# Schematic.net
KiCad netlist of a schematic drawn in Altium Designer
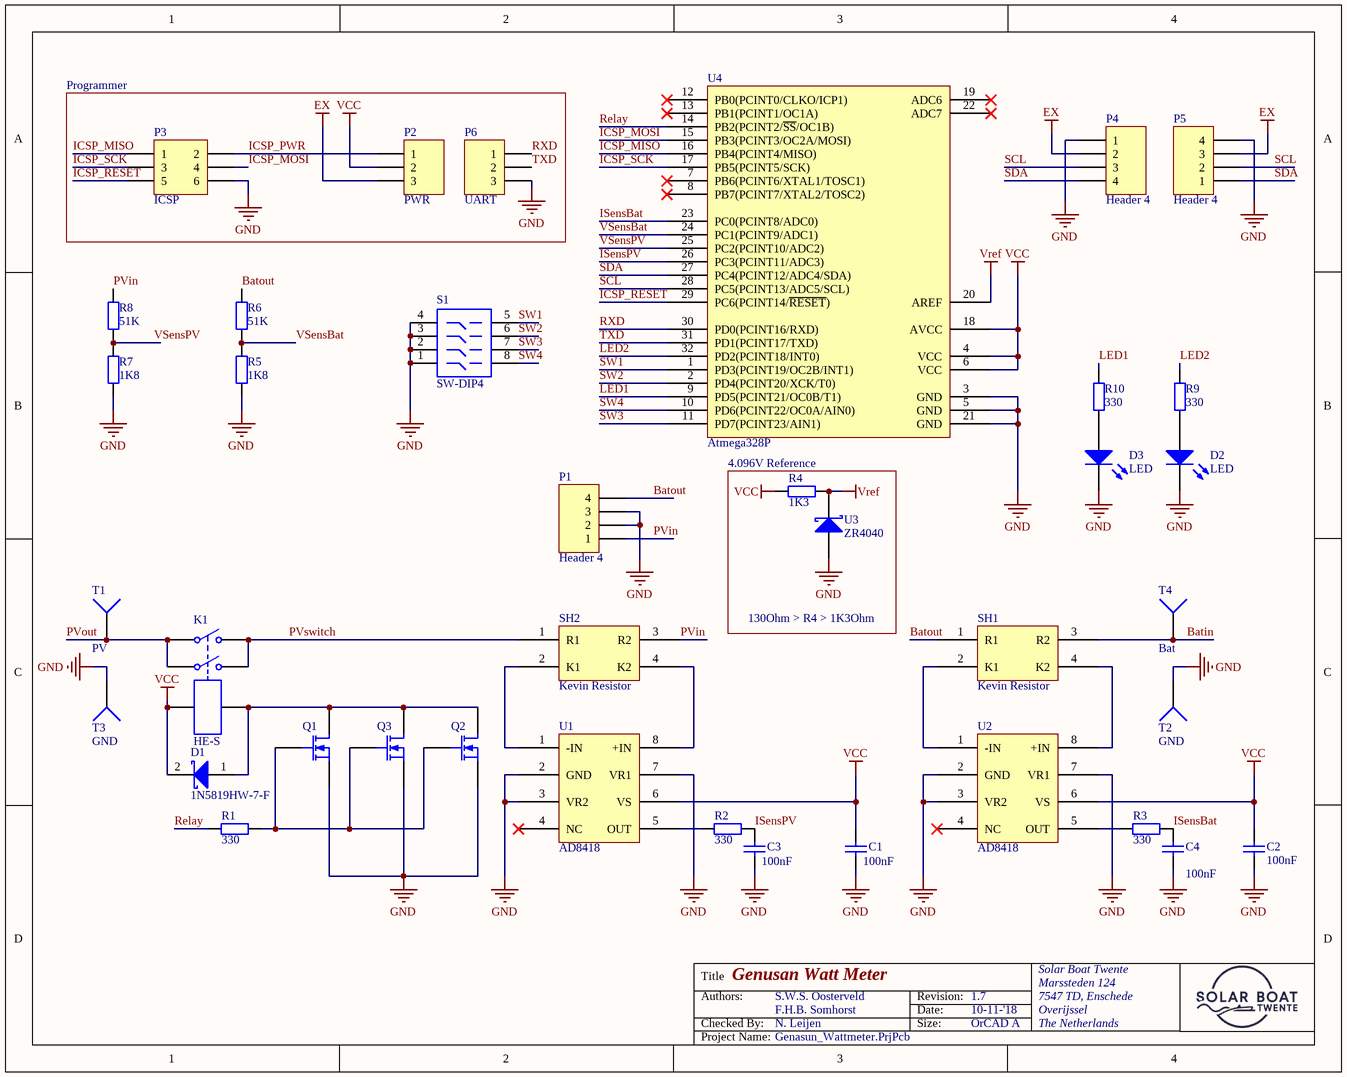
[diagram p0: Schematic.SchDoc]

(export (version "E")
  (design (tool "Eeschema 10.0.6"))
  (components
    (comp (ref "C1")
      (value "100nF")
      (footprint "CAP 0805/2012")
      (description "Capacitor")
      (fields (field (name "Comment") "Cap") (field (name "PUBLISHER") "Altium Limited"))
      (libsource (lib "Miscellaneous Devices") (part "Cap"))
    )
    (comp (ref "C2")
      (value "100nF")
      (footprint "CAP 0805/2012")
      (description "Capacitor")
      (fields (field (name "Comment") "Cap") (field (name "PUBLISHER") "Altium Limited"))
      (libsource (lib "Miscellaneous Devices") (part "Cap"))
    )
    (comp (ref "C3")
      (value "100nF")
      (footprint "CAP 0805/2012")
      (description "Capacitor")
      (fields (field (name "Comment") "Cap") (field (name "PUBLISHER") "Altium Limited"))
      (libsource (lib "Miscellaneous Devices") (part "Cap"))
    )
    (comp (ref "C4")
      (value "100nF")
      (footprint "CAP 0805/2012")
      (description "Capacitor")
      (fields (field (name "Comment") "Cap") (field (name "PUBLISHER") "Altium Limited"))
      (libsource (lib "Miscellaneous Devices") (part "Cap"))
    )
    (comp (ref "D1")
      (value "1N5819HW-7-F")
      (footprint "DIOD-SOD-123-2_V")
      (fields (field (name "MANUFACTURER") "Diodes Inc"))
      (libsource (lib "Altium Content Vault") (part "DIOD-DSKY-A1K2-2"))
    )
    (comp (ref "D2")
      (value "LED")
      (footprint "LED 0805/2012 RED")
      (description "Typical INFRARED GaAs LED")
      (fields (field (name "PUBLISHER") "Altium Limited"))
      (libsource (lib "Miscellaneous Devices") (part "LED0"))
    )
    (comp (ref "D3")
      (value "LED")
      (footprint "LED 0805/2012 RED")
      (description "Typical INFRARED GaAs LED")
      (fields (field (name "PUBLISHER") "Altium Limited"))
      (libsource (lib "Miscellaneous Devices") (part "LED0"))
    )
    (comp (ref "K1")
      (value "HE-S")
      (footprint "Relay HE-S Parasonic")
      (description "Dual-Pole Single-Throw Relay")
      (fields (field (name "PUBLISHER") "Altium Limited"))
      (libsource (lib "Miscellaneous Devices") (part "Relay-DPST"))
    )
    (comp (ref "P1")
      (value "Header 4")
      (footprint "4Pin 6.35mm Connector")
      (description "Header, 4-Pin")
      (fields (field (name "PUBLISHER") "Altium Limited"))
      (libsource (lib "Miscellaneous Connectors") (part "Header 4"))
    )
    (comp (ref "P2")
      (value "PWR")
      (footprint "HDR1X3")
      (description "Header, 3-Pin")
      (fields (field (name "PUBLISHER") "Altium Limited"))
      (libsource (lib "") (part "Header 3_1"))
    )
    (comp (ref "P3")
      (value "ICSP")
      (footprint "HDR2X3")
      (description "Header, 3-Pin, Dual row")
      (fields (field (name "PUBLISHER") "Altium Limited"))
      (libsource (lib "Miscellaneous Connectors") (part "Header 3X2"))
    )
    (comp (ref "P4")
      (value "Header 4")
      (footprint "TE 282834-4")
      (description "Header, 4-Pin")
      (fields (field (name "PUBLISHER") "Altium Limited"))
      (libsource (lib "") (part "Header 4_1"))
    )
    (comp (ref "P5")
      (value "Header 4")
      (footprint "TE 282834-4")
      (description "Header, 4-Pin")
      (fields (field (name "PUBLISHER") "Altium Limited"))
      (libsource (lib "Miscellaneous Connectors") (part "Header 4"))
    )
    (comp (ref "P6")
      (value "UART")
      (footprint "HDR1X3H")
      (description "Header, 3-Pin")
      (fields (field (name "PUBLISHER") "Altium Limited"))
      (libsource (lib "Miscellaneous Connectors") (part "Header 3"))
    )
    (comp (ref "Q1")
      (value "MOSFET-N")
      (footprint "DIODES SOT-23-3")
      (description "N-Channel MOSFET")
      (fields (field (name "PUBLISHER") "Altium Limited"))
      (libsource (lib "Miscellaneous Devices") (part "MOSFET-N"))
    )
    (comp (ref "Q2")
      (value "MOSFET-N")
      (footprint "DIODES SOT-23-3")
      (description "N-Channel MOSFET")
      (fields (field (name "PUBLISHER") "Altium Limited"))
      (libsource (lib "Miscellaneous Devices") (part "MOSFET-N"))
    )
    (comp (ref "Q3")
      (value "MOSFET-N")
      (footprint "DIODES SOT-23-3")
      (description "N-Channel MOSFET")
      (fields (field (name "PUBLISHER") "Altium Limited"))
      (libsource (lib "Miscellaneous Devices") (part "MOSFET-N"))
    )
    (comp (ref "R1")
      (value "330")
      (footprint "RES 0805/2012")
      (description "Resistor")
      (fields (field (name "Comment") "Res2") (field (name "PUBLISHER") "Altium Limited"))
      (libsource (lib "") (part "Res2_1"))
    )
    (comp (ref "R2")
      (value "330")
      (footprint "RES 0805/2012")
      (description "Resistor")
      (fields (field (name "Comment") "Res2") (field (name "PUBLISHER") "Altium Limited"))
      (libsource (lib "") (part "Res2_1"))
    )
    (comp (ref "R3")
      (value "330")
      (footprint "RES 0805/2012")
      (description "Resistor")
      (fields (field (name "Comment") "Res2") (field (name "PUBLISHER") "Altium Limited"))
      (libsource (lib "") (part "Res2_1"))
    )
    (comp (ref "R4")
      (value "1K3")
      (footprint "RES 0805/2012")
      (description "Resistor")
      (fields (field (name "Comment") "Res2") (field (name "PUBLISHER") "Altium Limited"))
      (libsource (lib "") (part "Res2_1"))
    )
    (comp (ref "R5")
      (value "1K8")
      (footprint "RES 0805/2012")
      (description "Resistor")
      (fields (field (name "Comment") "Res2") (field (name "PUBLISHER") "Altium Limited"))
      (libsource (lib "Miscellaneous Devices") (part "Res2"))
    )
    (comp (ref "R6")
      (value "51K")
      (footprint "RES 0805/2012")
      (description "Resistor")
      (fields (field (name "Comment") "Res2") (field (name "PUBLISHER") "Altium Limited"))
      (libsource (lib "Miscellaneous Devices") (part "Res2"))
    )
    (comp (ref "R7")
      (value "1K8")
      (footprint "RES 0805/2012")
      (description "Resistor")
      (fields (field (name "Comment") "Res2") (field (name "PUBLISHER") "Altium Limited"))
      (libsource (lib "Miscellaneous Devices") (part "Res2"))
    )
    (comp (ref "R8")
      (value "51K")
      (footprint "RES 0805/2012")
      (description "Resistor")
      (fields (field (name "Comment") "Res2") (field (name "PUBLISHER") "Altium Limited"))
      (libsource (lib "Miscellaneous Devices") (part "Res2"))
    )
    (comp (ref "R9")
      (value "330")
      (footprint "RES 0805/2012")
      (description "Resistor")
      (fields (field (name "Comment") "Res2") (field (name "PUBLISHER") "Altium Limited"))
      (libsource (lib "Miscellaneous Devices") (part "Res2"))
    )
    (comp (ref "R10")
      (value "330")
      (footprint "RES 0805/2012")
      (description "Resistor")
      (fields (field (name "Comment") "Res2") (field (name "PUBLISHER") "Altium Limited"))
      (libsource (lib "Miscellaneous Devices") (part "Res2"))
    )
    (comp (ref "S1")
      (value "SW-DIP4")
      (footprint "DIP-8")
      (description "DIP Switch")
      (fields (field (name "PUBLISHER") "Altium Limited"))
      (libsource (lib "Miscellaneous Devices") (part "SW-DIP4"))
    )
    (comp (ref "SH1")
      (value "Kevin Resistor")
      (footprint "TE TLR Shunt")
      (libsource (lib "Personal Library") (part "Kevin Resistor"))
    )
    (comp (ref "SH2")
      (value "Kevin Resistor")
      (footprint "TE TLR Shunt")
      (libsource (lib "Personal Library") (part "Kevin Resistor"))
    )
    (comp (ref "T1")
      (value "PV")
      (footprint "PCB_Pin_Outsteeksel")
      (description "Socket")
      (fields (field (name "PUBLISHER") "Altium Limited"))
      (libsource (lib "Miscellaneous Connectors") (part "Socket"))
    )
    (comp (ref "T2")
      (value "GND")
      (footprint "PCB_Pin_Outsteeksel")
      (description "Socket")
      (fields (field (name "PUBLISHER") "Altium Limited"))
      (libsource (lib "Miscellaneous Connectors") (part "Socket"))
    )
    (comp (ref "T3")
      (value "GND")
      (footprint "PCB_Pin_Outsteeksel")
      (description "Socket")
      (fields (field (name "PUBLISHER") "Altium Limited"))
      (libsource (lib "Miscellaneous Connectors") (part "Socket"))
    )
    (comp (ref "T4")
      (value "Bat")
      (footprint "PCB_Pin_Outsteeksel")
      (description "Socket")
      (fields (field (name "PUBLISHER") "Altium Limited"))
      (libsource (lib "Miscellaneous Connectors") (part "Socket"))
    )
    (comp (ref "U1")
      (value "AD8418")
      (footprint "INTERSIL MSOP-8 M8.118")
      (libsource (lib "GJ24") (part "AD8418"))
    )
    (comp (ref "U2")
      (value "AD8418")
      (footprint "INTERSIL MSOP-8 M8.118")
      (libsource (lib "GJ24") (part "AD8418"))
    )
    (comp (ref "U3")
      (value "ZR4040")
      (footprint "DIODES SOT-23-3")
      (description "Schottky Rectifier")
      (fields (field (name "PUBLISHER") "Altium Limited"))
      (libsource (lib "Miscellaneous Devices") (part "Diode 10TQ035"))
    )
    (comp (ref "U4")
      (value "Atmega328P")
      (footprint "ST LQFP-32 7X7MM")
      (libsource (lib "GJ24") (part "Atmega328P"))
    )
  )
  (nets
    (net (code "1") (name "/Batin") (class "Default")
      (node (ref "SH1") (pin "3") (pinfunction "R2_3") (pintype "passive"))
      (node (ref "T4") (pin "1") (pinfunction "1_1") (pintype "passive"))
    )
    (net (code "2") (name "/Batout") (class "Default")
      (node (ref "P1") (pin "4") (pinfunction "4_4") (pintype "passive"))
      (node (ref "R6") (pin "2") (pinfunction "2_2") (pintype "passive"))
      (node (ref "SH1") (pin "1") (pinfunction "R1_1") (pintype "passive"))
    )
    (net (code "3") (name "/ICSP_MISO") (class "Default")
      (node (ref "P3") (pin "1") (pinfunction "1_1") (pintype "passive"))
      (node (ref "U4") (pin "16") (pinfunction "PB4(PCINT4/MISO)_16") (pintype "passive"))
    )
    (net (code "4") (name "/ICSP_MOSI") (class "Default")
      (node (ref "P3") (pin "4") (pinfunction "4_4") (pintype "passive"))
      (node (ref "U4") (pin "15") (pinfunction "PB3(PCINT3/OC2A/MOSI)_15") (pintype "passive"))
    )
    (net (code "5") (name "/ICSP_PWR") (class "Default")
      (node (ref "P2") (pin "1") (pinfunction "1_1") (pintype "passive"))
      (node (ref "P3") (pin "2") (pinfunction "2_2") (pintype "passive"))
    )
    (net (code "6") (name "/ICSP_RESET") (class "Default")
      (node (ref "P3") (pin "5") (pinfunction "5_5") (pintype "passive"))
      (node (ref "U4") (pin "29") (pinfunction "PC6(PCINT14/~{RESET})_29") (pintype "passive"))
    )
    (net (code "7") (name "/ICSP_SCK") (class "Default")
      (node (ref "P3") (pin "3") (pinfunction "3_3") (pintype "passive"))
      (node (ref "U4") (pin "17") (pinfunction "PB5(PCINT5/SCK)_17") (pintype "passive"))
    )
    (net (code "8") (name "/ISensBat") (class "Default")
      (node (ref "C4") (pin "2") (pinfunction "2_2") (pintype "passive"))
      (node (ref "R3") (pin "1") (pinfunction "1_1") (pintype "passive"))
      (node (ref "U4") (pin "23") (pinfunction "PC0(PCINT8/ADC0)_23") (pintype "passive"))
    )
    (net (code "9") (name "/ISensPV") (class "Default")
      (node (ref "C3") (pin "2") (pinfunction "2_2") (pintype "passive"))
      (node (ref "R2") (pin "1") (pinfunction "1_1") (pintype "passive"))
      (node (ref "U4") (pin "26") (pinfunction "PC3(PCINT11/ADC3)_26") (pintype "passive"))
    )
    (net (code "10") (name "/LED1") (class "Default")
      (node (ref "R10") (pin "2") (pinfunction "2_2") (pintype "passive"))
      (node (ref "U4") (pin "9") (pinfunction "PD5(PCINT21/OC0B/T1)_9") (pintype "passive"))
    )
    (net (code "11") (name "/LED2") (class "Default")
      (node (ref "R9") (pin "2") (pinfunction "2_2") (pintype "passive"))
      (node (ref "U4") (pin "32") (pinfunction "PD2(PCINT18/INT0)_32") (pintype "passive"))
    )
    (net (code "12") (name "/PVin") (class "Default")
      (node (ref "P1") (pin "1") (pinfunction "1_1") (pintype "passive"))
      (node (ref "R8") (pin "2") (pinfunction "2_2") (pintype "passive"))
      (node (ref "SH2") (pin "3") (pinfunction "R2_3") (pintype "passive"))
    )
    (net (code "13") (name "/PVout") (class "Default")
      (node (ref "K1") (pin "1") (pinfunction "1_1") (pintype "passive"))
      (node (ref "K1") (pin "3") (pinfunction "3_3") (pintype "passive"))
      (node (ref "T1") (pin "1") (pinfunction "1_1") (pintype "passive"))
    )
    (net (code "14") (name "/PVswitch") (class "Default")
      (node (ref "K1") (pin "2") (pinfunction "2_2") (pintype "passive"))
      (node (ref "K1") (pin "4") (pinfunction "4_4") (pintype "passive"))
      (node (ref "SH2") (pin "1") (pinfunction "R1_1") (pintype "passive"))
    )
    (net (code "15") (name "/RXD") (class "Default")
      (node (ref "P6") (pin "1") (pinfunction "1_1") (pintype "passive"))
      (node (ref "U4") (pin "30") (pinfunction "PD0(PCINT16/RXD)_30") (pintype "passive"))
    )
    (net (code "16") (name "/Relay") (class "Default")
      (node (ref "R1") (pin "2") (pinfunction "2_2") (pintype "passive"))
      (node (ref "U4") (pin "14") (pinfunction "PB2(PCINT2/~{SS}/OC1B)_14") (pintype "passive"))
    )
    (net (code "17") (name "/SCL") (class "Default")
      (node (ref "P4") (pin "3") (pinfunction "3_3") (pintype "passive"))
      (node (ref "P5") (pin "2") (pinfunction "2_2") (pintype "passive"))
      (node (ref "U4") (pin "28") (pinfunction "PC5(PCINT13/ADC5/SCL)_28") (pintype "passive"))
    )
    (net (code "18") (name "/SDA") (class "Default")
      (node (ref "P4") (pin "4") (pinfunction "4_4") (pintype "passive"))
      (node (ref "P5") (pin "1") (pinfunction "1_1") (pintype "passive"))
      (node (ref "U4") (pin "27") (pinfunction "PC4(PCINT12/ADC4/SDA)_27") (pintype "passive"))
    )
    (net (code "19") (name "/SW1") (class "Default")
      (node (ref "S1") (pin "5") (pinfunction "5_5") (pintype "passive"))
      (node (ref "U4") (pin "1") (pinfunction "PD3(PCINT19/OC2B/INT1)_1") (pintype "passive"))
    )
    (net (code "20") (name "/SW2") (class "Default")
      (node (ref "S1") (pin "6") (pinfunction "6_6") (pintype "passive"))
      (node (ref "U4") (pin "2") (pinfunction "PD4(PCINT20/XCK/T0)_2") (pintype "passive"))
    )
    (net (code "21") (name "/SW3") (class "Default")
      (node (ref "S1") (pin "7") (pinfunction "7_7") (pintype "passive"))
      (node (ref "U4") (pin "11") (pinfunction "PD7(PCINT23/AIN1)_11") (pintype "passive"))
    )
    (net (code "22") (name "/SW4") (class "Default")
      (node (ref "S1") (pin "8") (pinfunction "8_8") (pintype "passive"))
      (node (ref "U4") (pin "10") (pinfunction "PD6(PCINT22/OC0A/AIN0)_10") (pintype "passive"))
    )
    (net (code "23") (name "/TXD") (class "Default")
      (node (ref "P6") (pin "2") (pinfunction "2_2") (pintype "passive"))
      (node (ref "U4") (pin "31") (pinfunction "PD1(PCINT17/TXD)_31") (pintype "passive"))
    )
    (net (code "24") (name "/VSensBat") (class "Default")
      (node (ref "R5") (pin "2") (pinfunction "2_2") (pintype "passive"))
      (node (ref "R6") (pin "1") (pinfunction "1_1") (pintype "passive"))
      (node (ref "U4") (pin "24") (pinfunction "PC1(PCINT9/ADC1)_24") (pintype "passive"))
    )
    (net (code "25") (name "/VSensPV") (class "Default")
      (node (ref "R7") (pin "2") (pinfunction "2_2") (pintype "passive"))
      (node (ref "R8") (pin "1") (pinfunction "1_1") (pintype "passive"))
      (node (ref "U4") (pin "25") (pinfunction "PC2(PCINT10/ADC2)_25") (pintype "passive"))
    )
    (net (code "26") (name "EX") (class "Default")
      (node (ref "P2") (pin "3") (pinfunction "3_3") (pintype "passive"))
      (node (ref "P4") (pin "2") (pinfunction "2_2") (pintype "passive"))
      (node (ref "P5") (pin "3") (pinfunction "3_3") (pintype "passive"))
    )
    (net (code "27") (name "GND") (class "Default")
      (node (ref "C1") (pin "1") (pinfunction "1_1") (pintype "passive"))
      (node (ref "C2") (pin "2") (pinfunction "2_2") (pintype "passive"))
      (node (ref "C3") (pin "1") (pinfunction "1_1") (pintype "passive"))
      (node (ref "C4") (pin "1") (pinfunction "1_1") (pintype "passive"))
      (node (ref "D2") (pin "2") (pinfunction "K_2") (pintype "passive"))
      (node (ref "D3") (pin "2") (pinfunction "K_2") (pintype "passive"))
      (node (ref "P1") (pin "2") (pinfunction "2_2") (pintype "passive"))
      (node (ref "P1") (pin "3") (pinfunction "3_3") (pintype "passive"))
      (node (ref "P3") (pin "6") (pinfunction "6_6") (pintype "passive"))
      (node (ref "P4") (pin "1") (pinfunction "1_1") (pintype "passive"))
      (node (ref "P5") (pin "4") (pinfunction "4_4") (pintype "passive"))
      (node (ref "P6") (pin "3") (pinfunction "3_3") (pintype "passive"))
      (node (ref "Q1") (pin "2") (pinfunction "S_2") (pintype "passive"))
      (node (ref "Q2") (pin "2") (pinfunction "S_2") (pintype "passive"))
      (node (ref "Q3") (pin "2") (pinfunction "S_2") (pintype "passive"))
      (node (ref "R5") (pin "1") (pinfunction "1_1") (pintype "passive"))
      (node (ref "R7") (pin "1") (pinfunction "1_1") (pintype "passive"))
      (node (ref "S1") (pin "1") (pinfunction "1_1") (pintype "passive"))
      (node (ref "S1") (pin "2") (pinfunction "2_2") (pintype "passive"))
      (node (ref "S1") (pin "3") (pinfunction "3_3") (pintype "passive"))
      (node (ref "S1") (pin "4") (pinfunction "4_4") (pintype "passive"))
      (node (ref "T2") (pin "1") (pinfunction "1_1") (pintype "passive"))
      (node (ref "T3") (pin "1") (pinfunction "1_1") (pintype "passive"))
      (node (ref "U1") (pin "2") (pinfunction "GND_2") (pintype "passive"))
      (node (ref "U1") (pin "3") (pinfunction "VR2_3") (pintype "passive"))
      (node (ref "U1") (pin "7") (pinfunction "VR1_7") (pintype "passive"))
      (node (ref "U2") (pin "2") (pinfunction "GND_2") (pintype "passive"))
      (node (ref "U2") (pin "3") (pinfunction "VR2_3") (pintype "passive"))
      (node (ref "U2") (pin "7") (pinfunction "VR1_7") (pintype "passive"))
      (node (ref "U3") (pin "3") (pinfunction "A_3") (pintype "passive"))
      (node (ref "U4") (pin "21") (pinfunction "GND_21") (pintype "passive"))
      (node (ref "U4") (pin "3") (pinfunction "GND_3") (pintype "passive"))
      (node (ref "U4") (pin "5") (pinfunction "GND_5") (pintype "passive"))
    )
    (net (code "28") (name "Net-(D1-A)") (class "Default")
      (node (ref "D1") (pin "1") (pinfunction "A_1") (pintype "passive"))
      (node (ref "K1") (pin "6") (pinfunction "6_6") (pintype "passive"))
      (node (ref "Q1") (pin "1") (pinfunction "D_1") (pintype "passive"))
      (node (ref "Q2") (pin "1") (pinfunction "D_1") (pintype "passive"))
      (node (ref "Q3") (pin "1") (pinfunction "D_1") (pintype "passive"))
    )
    (net (code "29") (name "Net-(D2-A)") (class "Default")
      (node (ref "D2") (pin "1") (pinfunction "A_1") (pintype "passive"))
      (node (ref "R9") (pin "1") (pinfunction "1_1") (pintype "passive"))
    )
    (net (code "30") (name "Net-(D3-A)") (class "Default")
      (node (ref "D3") (pin "1") (pinfunction "A_1") (pintype "passive"))
      (node (ref "R10") (pin "1") (pinfunction "1_1") (pintype "passive"))
    )
    (net (code "31") (name "Net-(Q1-G)") (class "Default")
      (node (ref "Q1") (pin "3") (pinfunction "G_3") (pintype "passive"))
      (node (ref "Q2") (pin "3") (pinfunction "G_3") (pintype "passive"))
      (node (ref "Q3") (pin "3") (pinfunction "G_3") (pintype "passive"))
      (node (ref "R1") (pin "1") (pinfunction "1_1") (pintype "passive"))
    )
    (net (code "32") (name "Net-(SH1-K1)") (class "Default")
      (node (ref "SH1") (pin "2") (pinfunction "K1_2") (pintype "passive"))
      (node (ref "U2") (pin "1") (pinfunction "-IN_1") (pintype "passive"))
    )
    (net (code "33") (name "Net-(SH1-K2)") (class "Default")
      (node (ref "SH1") (pin "4") (pinfunction "K2_4") (pintype "passive"))
      (node (ref "U2") (pin "8") (pinfunction "+IN_8") (pintype "passive"))
    )
    (net (code "34") (name "Net-(SH2-K1)") (class "Default")
      (node (ref "SH2") (pin "2") (pinfunction "K1_2") (pintype "passive"))
      (node (ref "U1") (pin "1") (pinfunction "-IN_1") (pintype "passive"))
    )
    (net (code "35") (name "Net-(SH2-K2)") (class "Default")
      (node (ref "SH2") (pin "4") (pinfunction "K2_4") (pintype "passive"))
      (node (ref "U1") (pin "8") (pinfunction "+IN_8") (pintype "passive"))
    )
    (net (code "36") (name "Net-(U1-OUT)") (class "Default")
      (node (ref "R2") (pin "2") (pinfunction "2_2") (pintype "passive"))
      (node (ref "U1") (pin "5") (pinfunction "OUT_5") (pintype "passive"))
    )
    (net (code "37") (name "Net-(U2-OUT)") (class "Default")
      (node (ref "R3") (pin "2") (pinfunction "2_2") (pintype "passive"))
      (node (ref "U2") (pin "5") (pinfunction "OUT_5") (pintype "passive"))
    )
    (net (code "38") (name "VCC") (class "Default")
      (node (ref "C1") (pin "2") (pinfunction "2_2") (pintype "passive"))
      (node (ref "C2") (pin "1") (pinfunction "1_1") (pintype "passive"))
      (node (ref "D1") (pin "2") (pinfunction "K_2") (pintype "passive"))
      (node (ref "K1") (pin "5") (pinfunction "5_5") (pintype "passive"))
      (node (ref "P2") (pin "2") (pinfunction "2_2") (pintype "passive"))
      (node (ref "R4") (pin "2") (pinfunction "2_2") (pintype "passive"))
      (node (ref "U1") (pin "6") (pinfunction "VS_6") (pintype "passive"))
      (node (ref "U2") (pin "6") (pinfunction "VS_6") (pintype "passive"))
      (node (ref "U4") (pin "18") (pinfunction "AVCC_18") (pintype "passive"))
      (node (ref "U4") (pin "4") (pinfunction "VCC_4") (pintype "passive"))
      (node (ref "U4") (pin "6") (pinfunction "VCC_6") (pintype "passive"))
    )
    (net (code "39") (name "Vref") (class "Default")
      (node (ref "R4") (pin "1") (pinfunction "1_1") (pintype "passive"))
      (node (ref "U3") (pin "1") (pinfunction "K_1") (pintype "passive"))
      (node (ref "U4") (pin "20") (pinfunction "AREF_20") (pintype "passive"))
    )
    (net (code "40") (name "unconnected-(U1-NC-Pad4)") (class "Default")
      (node (ref "U1") (pin "4") (pinfunction "NC_4") (pintype "passive+no_connect"))
    )
    (net (code "41") (name "unconnected-(U2-NC-Pad4)") (class "Default")
      (node (ref "U2") (pin "4") (pinfunction "NC_4") (pintype "passive+no_connect"))
    )
    (net (code "42") (name "unconnected-(U4-ADC6-Pad19)") (class "Default")
      (node (ref "U4") (pin "19") (pinfunction "ADC6_19") (pintype "passive+no_connect"))
    )
    (net (code "43") (name "unconnected-(U4-ADC7-Pad22)") (class "Default")
      (node (ref "U4") (pin "22") (pinfunction "ADC7_22") (pintype "passive+no_connect"))
    )
    (net (code "44") (name "unconnected-(U4-PB0(PCINT0{slash}CLKO{slash}ICP1)-Pad12)") (class "Default")
      (node (ref "U4") (pin "12") (pinfunction "PB0(PCINT0/CLKO/ICP1)_12") (pintype "passive+no_connect"))
    )
    (net (code "45") (name "unconnected-(U4-PB1(PCINT1{slash}OC1A)-Pad13)") (class "Default")
      (node (ref "U4") (pin "13") (pinfunction "PB1(PCINT1/OC1A)_13") (pintype "passive+no_connect"))
    )
    (net (code "46") (name "unconnected-(U4-PB6(PCINT6{slash}XTAL1{slash}TOSC1)-Pad7)") (class "Default")
      (node (ref "U4") (pin "7") (pinfunction "PB6(PCINT6/XTAL1/TOSC1)_7") (pintype "passive+no_connect"))
    )
    (net (code "47") (name "unconnected-(U4-PB7(PCINT7{slash}XTAL2{slash}TOSC2)-Pad8)") (class "Default")
      (node (ref "U4") (pin "8") (pinfunction "PB7(PCINT7/XTAL2/TOSC2)_8") (pintype "passive+no_connect"))
    )
  )
)
